# RP2350B.net
KiCad netlist of a schematic drawn in Altium Designer
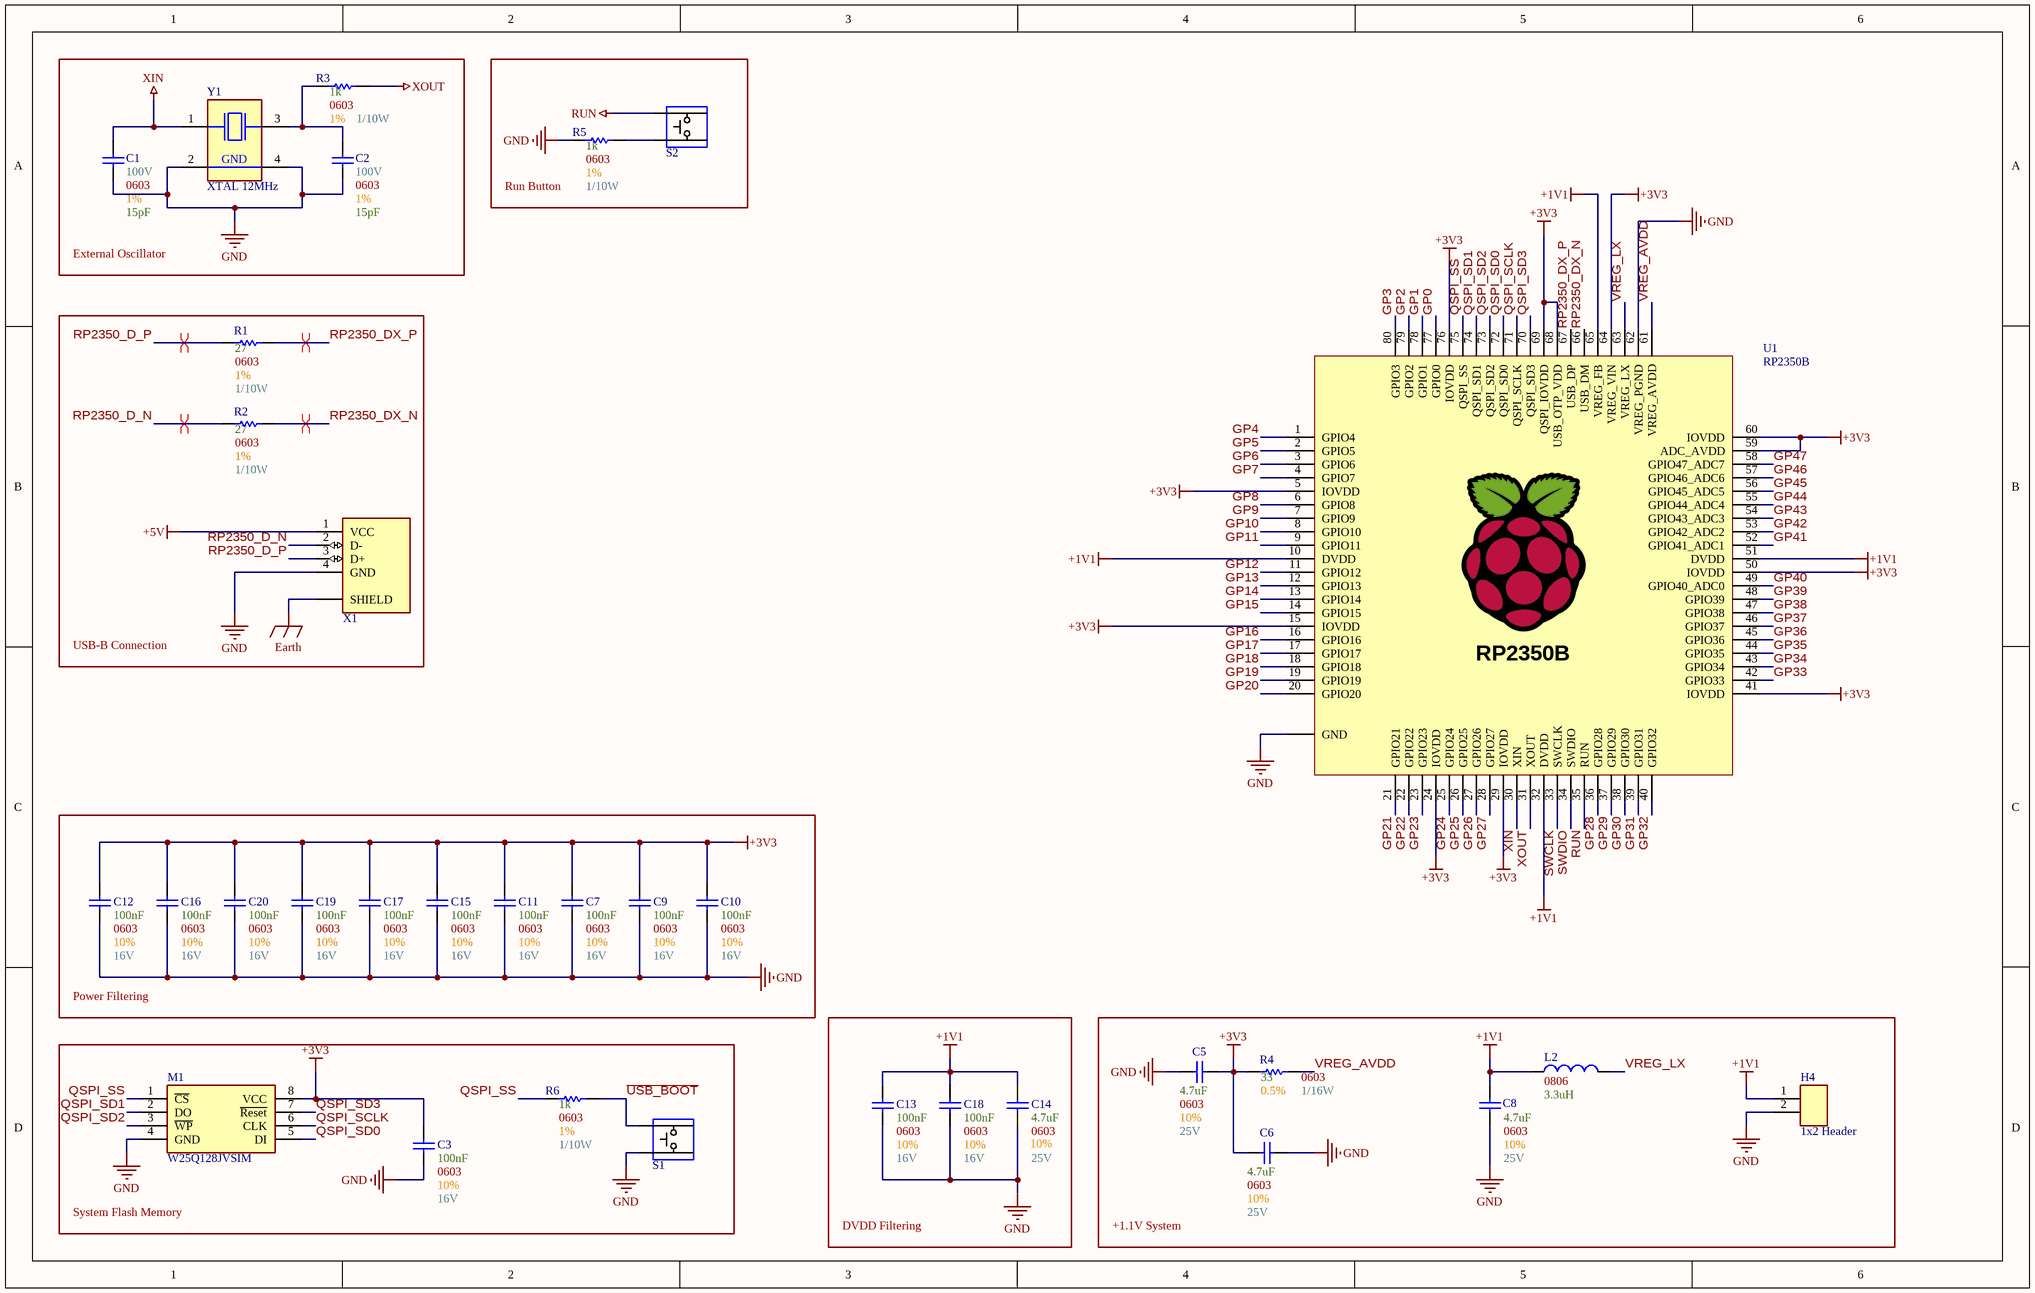
[diagram p0: RP2350B.SchDoc]

(export (version "E")
  (design (tool "Eeschema 10.0.6"))
  (components
    (comp (ref "C1")
      (value "[Cap] 0603 15pF 1% 100V")
      (footprint "[Cap] SMD 0603")
      (description "GCM1885C2A150FA16D")
      (fields
        (field (name "MAX VOLTAGE") "100V")
        (field (name "SIZE PACKAGE") "0603")
        (field (name "TOLERANCE") "1%")
        (field (name "CAPACITANCE") "15pF")
      )
      (libsource (lib "Capacitors") (part "[Cap] 0603 15pF 1% 100V"))
    )
    (comp (ref "C2")
      (value "[Cap] 0603 15pF 1% 100V")
      (footprint "[Cap] SMD 0603")
      (description "GCM1885C2A150FA16D")
      (fields
        (field (name "MAX VOLTAGE") "100V")
        (field (name "SIZE PACKAGE") "0603")
        (field (name "TOLERANCE") "1%")
        (field (name "CAPACITANCE") "15pF")
      )
      (libsource (lib "Capacitors") (part "[Cap] 0603 15pF 1% 100V"))
    )
    (comp (ref "C3")
      (value "[Cap] 0603 0.1uF 10% 16V")
      (footprint "[Cap] SMD 0603")
      (description "CC0603KRX7R7BB104")
      (fields
        (field (name "MAX VOLTAGE") "16V")
        (field (name "SIZE PACKAGE") "0603")
        (field (name "TOLERANCE") "10%")
        (field (name "CAPACITANCE") "100nF")
      )
      (libsource (lib "Capacitors") (part "[Cap] 0603 0.1uF 10% 16V"))
    )
    (comp (ref "C5")
      (value "[Cap] 0603 4.7uF 10% 25V")
      (footprint "[Cap] SMD 0603")
      (description "GRM188R61E475KE11D")
      (fields
        (field (name "MAX VOLTAGE") "25V")
        (field (name "SIZE PACKAGE") "0603")
        (field (name "TOLERANCE") "10%")
        (field (name "CAPACITANCE") "4.7uF")
      )
      (libsource (lib "Capacitors") (part "[Cap] 0603 4.7uF 10% 25V"))
    )
    (comp (ref "C6")
      (value "[Cap] 0603 4.7uF 10% 25V")
      (footprint "[Cap] SMD 0603")
      (description "GRM188R61E475KE11D")
      (fields
        (field (name "MAX VOLTAGE") "25V")
        (field (name "SIZE PACKAGE") "0603")
        (field (name "TOLERANCE") "10%")
        (field (name "CAPACITANCE") "4.7uF")
      )
      (libsource (lib "Capacitors") (part "[Cap] 0603 4.7uF 10% 25V"))
    )
    (comp (ref "C7")
      (value "[Cap] 0603 0.1uF 10% 16V")
      (footprint "[Cap] SMD 0603")
      (description "CC0603KRX7R7BB104")
      (fields
        (field (name "MAX VOLTAGE") "16V")
        (field (name "SIZE PACKAGE") "0603")
        (field (name "TOLERANCE") "10%")
        (field (name "CAPACITANCE") "100nF")
      )
      (libsource (lib "Capacitors") (part "[Cap] 0603 0.1uF 10% 16V"))
    )
    (comp (ref "C8")
      (value "[Cap] 0603 4.7uF 10% 25V")
      (footprint "[Cap] SMD 0603")
      (description "GRM188R61E475KE11D")
      (fields
        (field (name "MAX VOLTAGE") "25V")
        (field (name "SIZE PACKAGE") "0603")
        (field (name "TOLERANCE") "10%")
        (field (name "CAPACITANCE") "4.7uF")
      )
      (libsource (lib "Capacitors") (part "[Cap] 0603 4.7uF 10% 25V"))
    )
    (comp (ref "C9")
      (value "[Cap] 0603 0.1uF 10% 16V")
      (footprint "[Cap] SMD 0603")
      (description "CC0603KRX7R7BB104")
      (fields
        (field (name "MAX VOLTAGE") "16V")
        (field (name "SIZE PACKAGE") "0603")
        (field (name "TOLERANCE") "10%")
        (field (name "CAPACITANCE") "100nF")
      )
      (libsource (lib "Capacitors") (part "[Cap] 0603 0.1uF 10% 16V"))
    )
    (comp (ref "C10")
      (value "[Cap] 0603 0.1uF 10% 16V")
      (footprint "[Cap] SMD 0603")
      (description "CC0603KRX7R7BB104")
      (fields
        (field (name "MAX VOLTAGE") "16V")
        (field (name "SIZE PACKAGE") "0603")
        (field (name "TOLERANCE") "10%")
        (field (name "CAPACITANCE") "100nF")
      )
      (libsource (lib "Capacitors") (part "[Cap] 0603 0.1uF 10% 16V"))
    )
    (comp (ref "C11")
      (value "[Cap] 0603 0.1uF 10% 16V")
      (footprint "[Cap] SMD 0603")
      (description "CC0603KRX7R7BB104")
      (fields
        (field (name "MAX VOLTAGE") "16V")
        (field (name "SIZE PACKAGE") "0603")
        (field (name "TOLERANCE") "10%")
        (field (name "CAPACITANCE") "100nF")
      )
      (libsource (lib "Capacitors") (part "[Cap] 0603 0.1uF 10% 16V"))
    )
    (comp (ref "C12")
      (value "[Cap] 0603 0.1uF 10% 16V")
      (footprint "[Cap] SMD 0603")
      (description "CC0603KRX7R7BB104")
      (fields
        (field (name "MAX VOLTAGE") "16V")
        (field (name "SIZE PACKAGE") "0603")
        (field (name "TOLERANCE") "10%")
        (field (name "CAPACITANCE") "100nF")
      )
      (libsource (lib "Capacitors") (part "[Cap] 0603 0.1uF 10% 16V"))
    )
    (comp (ref "C13")
      (value "[Cap] 0603 0.1uF 10% 16V")
      (footprint "[Cap] SMD 0603")
      (description "CC0603KRX7R7BB104")
      (fields
        (field (name "MAX VOLTAGE") "16V")
        (field (name "SIZE PACKAGE") "0603")
        (field (name "TOLERANCE") "10%")
        (field (name "CAPACITANCE") "100nF")
      )
      (libsource (lib "Capacitors") (part "[Cap] 0603 0.1uF 10% 16V"))
    )
    (comp (ref "C14")
      (value "[Cap] 0603 4.7uF 10% 25V")
      (footprint "[Cap] SMD 0603")
      (description "GRM188R61E475KE11D")
      (fields
        (field (name "MAX VOLTAGE") "25V")
        (field (name "SIZE PACKAGE") "0603")
        (field (name "TOLERANCE") "10%")
        (field (name "CAPACITANCE") "4.7uF")
      )
      (libsource (lib "Capacitors") (part "[Cap] 0603 4.7uF 10% 25V"))
    )
    (comp (ref "C15")
      (value "[Cap] 0603 0.1uF 10% 16V")
      (footprint "[Cap] SMD 0603")
      (description "CC0603KRX7R7BB104")
      (fields
        (field (name "MAX VOLTAGE") "16V")
        (field (name "SIZE PACKAGE") "0603")
        (field (name "TOLERANCE") "10%")
        (field (name "CAPACITANCE") "100nF")
      )
      (libsource (lib "Capacitors") (part "[Cap] 0603 0.1uF 10% 16V"))
    )
    (comp (ref "C16")
      (value "[Cap] 0603 0.1uF 10% 16V")
      (footprint "[Cap] SMD 0603")
      (description "CC0603KRX7R7BB104")
      (fields
        (field (name "MAX VOLTAGE") "16V")
        (field (name "SIZE PACKAGE") "0603")
        (field (name "TOLERANCE") "10%")
        (field (name "CAPACITANCE") "100nF")
      )
      (libsource (lib "Capacitors") (part "[Cap] 0603 0.1uF 10% 16V"))
    )
    (comp (ref "C17")
      (value "[Cap] 0603 0.1uF 10% 16V")
      (footprint "[Cap] SMD 0603")
      (description "CC0603KRX7R7BB104")
      (fields
        (field (name "MAX VOLTAGE") "16V")
        (field (name "SIZE PACKAGE") "0603")
        (field (name "TOLERANCE") "10%")
        (field (name "CAPACITANCE") "100nF")
      )
      (libsource (lib "Capacitors") (part "[Cap] 0603 0.1uF 10% 16V"))
    )
    (comp (ref "C18")
      (value "[Cap] 0603 0.1uF 10% 16V")
      (footprint "[Cap] SMD 0603")
      (description "CC0603KRX7R7BB104")
      (fields
        (field (name "MAX VOLTAGE") "16V")
        (field (name "SIZE PACKAGE") "0603")
        (field (name "TOLERANCE") "10%")
        (field (name "CAPACITANCE") "100nF")
      )
      (libsource (lib "Capacitors") (part "[Cap] 0603 0.1uF 10% 16V"))
    )
    (comp (ref "C19")
      (value "[Cap] 0603 0.1uF 10% 16V")
      (footprint "[Cap] SMD 0603")
      (description "CC0603KRX7R7BB104")
      (fields
        (field (name "MAX VOLTAGE") "16V")
        (field (name "SIZE PACKAGE") "0603")
        (field (name "TOLERANCE") "10%")
        (field (name "CAPACITANCE") "100nF")
      )
      (libsource (lib "Capacitors") (part "[Cap] 0603 0.1uF 10% 16V"))
    )
    (comp (ref "C20")
      (value "[Cap] 0603 0.1uF 10% 16V")
      (footprint "[Cap] SMD 0603")
      (description "CC0603KRX7R7BB104")
      (fields
        (field (name "MAX VOLTAGE") "16V")
        (field (name "SIZE PACKAGE") "0603")
        (field (name "TOLERANCE") "10%")
        (field (name "CAPACITANCE") "100nF")
      )
      (libsource (lib "Capacitors") (part "[Cap] 0603 0.1uF 10% 16V"))
    )
    (comp (ref "H4")
      (value "1x2 Header")
      (footprint "[Header] 1x2 Male")
      (description "2.54mm pitch")
      (libsource (lib "Connectors") (part "[Header] 1x2 Male"))
    )
    (comp (ref "L2")
      (value "[3.3uH] SMD 0806 2.1A")
      (footprint "[Inductor] SMD 0806")
      (description "AOTA-B201610S3R3-101-T")
      (fields (field (name "PACKAGE") "0806") (field (name "INDUCTANCE") "3.3uH"))
      (libsource (lib "Inductors") (part "[3.3uH] SMD 0806 2.1A"))
    )
    (comp (ref "M1")
      (value "W25Q128JVSIM")
      (footprint "[Flash] 128MBit")
      (libsource (lib "Memory") (part "[Flash] 128MBit"))
    )
    (comp (ref "R1")
      (value "[27] SMD 0603 1% 1/10W")
      (footprint "[Res] SMD 0603")
      (description "MCT06030C2709FP500")
      (fields
        (field (name "WATTAGE") "1/10W")
        (field (name "TOLERANCE") "1%")
        (field (name "RESISTANCE") "27")
        (field (name "SIZE PACKAGE") "0603")
      )
      (libsource (lib "Resistors") (part "[27] SMD 0603 1% 1/10W"))
    )
    (comp (ref "R2")
      (value "[27] SMD 0603 1% 1/10W")
      (footprint "[Res] SMD 0603")
      (description "MCT06030C2709FP500")
      (fields
        (field (name "WATTAGE") "1/10W")
        (field (name "TOLERANCE") "1%")
        (field (name "RESISTANCE") "27")
        (field (name "SIZE PACKAGE") "0603")
      )
      (libsource (lib "Resistors") (part "[27] SMD 0603 1% 1/10W"))
    )
    (comp (ref "R3")
      (value "[1k] SMD 0603 1% 1/10W")
      (footprint "[Res] SMD 0603")
      (description "RMCF0603FT1K00")
      (fields
        (field (name "WATTAGE") "1/10W")
        (field (name "TOLERANCE") "1%")
        (field (name "RESISTANCE") "1k")
        (field (name "SIZE PACKAGE") "0603")
      )
      (libsource (lib "Resistors") (part "[1k] SMD 0603 1% 1/10W"))
    )
    (comp (ref "R4")
      (value "[33] SMD 0603 0.5% 1/16W")
      (footprint "[Res] SMD 0603")
      (description "RR0816Q-330-D")
      (fields
        (field (name "WATTAGE") "1/16W")
        (field (name "TOLERANCE") "0.5%")
        (field (name "RESISTANCE") "33")
        (field (name "SIZE PACKAGE") "0603")
      )
      (libsource (lib "Resistors") (part "[33] SMD 0603 0.5% 1/16W"))
    )
    (comp (ref "R5")
      (value "[1k] SMD 0603 1% 1/10W")
      (footprint "[Res] SMD 0603")
      (description "RMCF0603FT1K00")
      (fields
        (field (name "WATTAGE") "1/10W")
        (field (name "TOLERANCE") "1%")
        (field (name "RESISTANCE") "1k")
        (field (name "SIZE PACKAGE") "0603")
      )
      (libsource (lib "Resistors") (part "[1k] SMD 0603 1% 1/10W"))
    )
    (comp (ref "R6")
      (value "[1k] SMD 0603 1% 1/10W")
      (footprint "[Res] SMD 0603")
      (description "RMCF0603FT1K00")
      (fields
        (field (name "WATTAGE") "1/10W")
        (field (name "TOLERANCE") "1%")
        (field (name "RESISTANCE") "1k")
        (field (name "SIZE PACKAGE") "0603")
      )
      (libsource (lib "Resistors") (part "[1k] SMD 0603 1% 1/10W"))
    )
    (comp (ref "S1")
      (value "Standard pushbutton")
      (footprint "[SPST] Pushbutton")
      (libsource (lib "Switches") (part "[SPST] Pushbutton"))
    )
    (comp (ref "S2")
      (value "Standard pushbutton")
      (footprint "[SPST] Pushbutton")
      (libsource (lib "Switches") (part "[SPST] Pushbutton"))
    )
    (comp (ref "U1")
      (value "RP2350B")
      (footprint "[MCU] RP2350B")
      (description "QFN-80 Package")
      (libsource (lib "MCUs") (part "[MCU] RP2350B"))
    )
    (comp (ref "X1")
      (value "USB-B")
      (footprint "[USB] Type-B")
      (description "USB-B-S-F-B-TH")
      (libsource (lib "Connectors") (part "[USB] Type-B"))
    )
    (comp (ref "Y1")
      (value "XTAL 12MHz")
      (footprint "[Crystal] SMD 12MHz")
      (description "815-ABM8-272-T3")
      (libsource (lib "Crystals and Oscillators") (part "[Crystal] SMD 12MHz"))
    )
  )
  (nets
    (net (code "1") (name "+1V1") (class "Default")
      (node (ref "C13") (pin "2") (pinfunction "2_2") (pintype "passive"))
      (node (ref "C14") (pin "2") (pinfunction "2_2") (pintype "passive"))
      (node (ref "C18") (pin "2") (pinfunction "2_2") (pintype "passive"))
      (node (ref "C8") (pin "1") (pinfunction "1_1") (pintype "passive"))
      (node (ref "H4") (pin "1") (pintype "passive"))
      (node (ref "L2") (pin "1") (pinfunction "1_1") (pintype "passive"))
      (node (ref "U1") (pin "10") (pinfunction "DVDD_10") (pintype "passive"))
      (node (ref "U1") (pin "32") (pinfunction "DVDD_32") (pintype "passive"))
      (node (ref "U1") (pin "51") (pinfunction "DVDD_51") (pintype "passive"))
      (node (ref "U1") (pin "65") (pinfunction "VREG_FB_65") (pintype "passive"))
    )
    (net (code "2") (name "+3V3") (class "Default")
      (node (ref "C10") (pin "2") (pinfunction "2_2") (pintype "passive"))
      (node (ref "C11") (pin "2") (pinfunction "2_2") (pintype "passive"))
      (node (ref "C12") (pin "2") (pinfunction "2_2") (pintype "passive"))
      (node (ref "C15") (pin "2") (pinfunction "2_2") (pintype "passive"))
      (node (ref "C16") (pin "2") (pinfunction "2_2") (pintype "passive"))
      (node (ref "C17") (pin "2") (pinfunction "2_2") (pintype "passive"))
      (node (ref "C19") (pin "2") (pinfunction "2_2") (pintype "passive"))
      (node (ref "C20") (pin "2") (pinfunction "2_2") (pintype "passive"))
      (node (ref "C3") (pin "2") (pinfunction "2_2") (pintype "passive"))
      (node (ref "C5") (pin "1") (pinfunction "1_1") (pintype "passive"))
      (node (ref "C6") (pin "2") (pinfunction "2_2") (pintype "passive"))
      (node (ref "C7") (pin "2") (pinfunction "2_2") (pintype "passive"))
      (node (ref "C9") (pin "2") (pinfunction "2_2") (pintype "passive"))
      (node (ref "M1") (pin "8") (pinfunction "VCC_8") (pintype "passive"))
      (node (ref "R4") (pin "1") (pinfunction "1_1") (pintype "passive"))
      (node (ref "U1") (pin "15") (pinfunction "IOVDD_15") (pintype "passive"))
      (node (ref "U1") (pin "24") (pinfunction "IOVDD_24") (pintype "passive"))
      (node (ref "U1") (pin "29") (pinfunction "IOVDD_29") (pintype "passive"))
      (node (ref "U1") (pin "41") (pinfunction "IOVDD_41") (pintype "passive"))
      (node (ref "U1") (pin "5") (pinfunction "IOVDD_5") (pintype "passive"))
      (node (ref "U1") (pin "50") (pinfunction "IOVDD_50") (pintype "passive"))
      (node (ref "U1") (pin "59") (pinfunction "ADC_AVDD_59") (pintype "passive"))
      (node (ref "U1") (pin "60") (pinfunction "IOVDD_60") (pintype "passive"))
      (node (ref "U1") (pin "64") (pinfunction "VREG_VIN_64") (pintype "passive"))
      (node (ref "U1") (pin "68") (pinfunction "USB_OTP_VDD_68") (pintype "passive"))
      (node (ref "U1") (pin "69") (pinfunction "QSPI_IOVDD_69") (pintype "passive"))
      (node (ref "U1") (pin "76") (pinfunction "IOVDD_76") (pintype "passive"))
    )
    (net (code "3") (name "+5V") (class "Default")
      (node (ref "X1") (pin "1") (pinfunction "VCC_1") (pintype "power_in"))
    )
    (net (code "4") (name "/GP0") (class "Default")
      (node (ref "U1") (pin "77") (pinfunction "GPIO0_77") (pintype "passive"))
    )
    (net (code "5") (name "/GP1") (class "Default")
      (node (ref "U1") (pin "78") (pinfunction "GPIO1_78") (pintype "passive"))
    )
    (net (code "6") (name "/GP2") (class "Default")
      (node (ref "U1") (pin "79") (pinfunction "GPIO2_79") (pintype "passive"))
    )
    (net (code "7") (name "/GP3") (class "Default")
      (node (ref "U1") (pin "80") (pinfunction "GPIO3_80") (pintype "passive"))
    )
    (net (code "8") (name "/GP4") (class "Default")
      (node (ref "U1") (pin "1") (pinfunction "GPIO4_1") (pintype "passive"))
    )
    (net (code "9") (name "/GP5") (class "Default")
      (node (ref "U1") (pin "2") (pinfunction "GPIO5_2") (pintype "passive"))
    )
    (net (code "10") (name "/GP6") (class "Default")
      (node (ref "U1") (pin "3") (pinfunction "GPIO6_3") (pintype "passive"))
    )
    (net (code "11") (name "/GP7") (class "Default")
      (node (ref "U1") (pin "4") (pinfunction "GPIO7_4") (pintype "passive"))
    )
    (net (code "12") (name "/GP8") (class "Default")
      (node (ref "U1") (pin "6") (pinfunction "GPIO8_6") (pintype "passive"))
    )
    (net (code "13") (name "/GP9") (class "Default")
      (node (ref "U1") (pin "7") (pinfunction "GPIO9_7") (pintype "passive"))
    )
    (net (code "14") (name "/GP10") (class "Default")
      (node (ref "U1") (pin "8") (pinfunction "GPIO10_8") (pintype "passive"))
    )
    (net (code "15") (name "/GP11") (class "Default")
      (node (ref "U1") (pin "9") (pinfunction "GPIO11_9") (pintype "passive"))
    )
    (net (code "16") (name "/GP12") (class "Default")
      (node (ref "U1") (pin "11") (pinfunction "GPIO12_11") (pintype "passive"))
    )
    (net (code "17") (name "/GP13") (class "Default")
      (node (ref "U1") (pin "12") (pinfunction "GPIO13_12") (pintype "passive"))
    )
    (net (code "18") (name "/GP14") (class "Default")
      (node (ref "U1") (pin "13") (pinfunction "GPIO14_13") (pintype "passive"))
    )
    (net (code "19") (name "/GP15") (class "Default")
      (node (ref "U1") (pin "14") (pinfunction "GPIO15_14") (pintype "passive"))
    )
    (net (code "20") (name "/GP16") (class "Default")
      (node (ref "U1") (pin "16") (pinfunction "GPIO16_16") (pintype "passive"))
    )
    (net (code "21") (name "/GP17") (class "Default")
      (node (ref "U1") (pin "17") (pinfunction "GPIO17_17") (pintype "passive"))
    )
    (net (code "22") (name "/GP18") (class "Default")
      (node (ref "U1") (pin "18") (pinfunction "GPIO18_18") (pintype "passive"))
    )
    (net (code "23") (name "/GP19") (class "Default")
      (node (ref "U1") (pin "19") (pinfunction "GPIO19_19") (pintype "passive"))
    )
    (net (code "24") (name "/GP20") (class "Default")
      (node (ref "U1") (pin "20") (pinfunction "GPIO20_20") (pintype "passive"))
    )
    (net (code "25") (name "/GP21") (class "Default")
      (node (ref "U1") (pin "21") (pinfunction "GPIO21_21") (pintype "passive"))
    )
    (net (code "26") (name "/GP22") (class "Default")
      (node (ref "U1") (pin "22") (pinfunction "GPIO22_22") (pintype "passive"))
    )
    (net (code "27") (name "/GP23") (class "Default")
      (node (ref "U1") (pin "23") (pinfunction "GPIO23_23") (pintype "passive"))
    )
    (net (code "28") (name "/GP24") (class "Default")
      (node (ref "U1") (pin "25") (pinfunction "GPIO24_25") (pintype "passive"))
    )
    (net (code "29") (name "/GP25") (class "Default")
      (node (ref "U1") (pin "26") (pinfunction "GPIO25_26") (pintype "passive"))
    )
    (net (code "30") (name "/GP26") (class "Default")
      (node (ref "U1") (pin "27") (pinfunction "GPIO26_27") (pintype "passive"))
    )
    (net (code "31") (name "/GP27") (class "Default")
      (node (ref "U1") (pin "28") (pinfunction "GPIO27_28") (pintype "passive"))
    )
    (net (code "32") (name "/GP28") (class "Default")
      (node (ref "U1") (pin "36") (pinfunction "GPIO28_36") (pintype "passive"))
    )
    (net (code "33") (name "/GP29") (class "Default")
      (node (ref "U1") (pin "37") (pinfunction "GPIO29_37") (pintype "passive"))
    )
    (net (code "34") (name "/GP30") (class "Default")
      (node (ref "U1") (pin "38") (pinfunction "GPIO30_38") (pintype "passive"))
    )
    (net (code "35") (name "/GP31") (class "Default")
      (node (ref "U1") (pin "39") (pinfunction "GPIO31_39") (pintype "passive"))
    )
    (net (code "36") (name "/GP32") (class "Default")
      (node (ref "U1") (pin "40") (pinfunction "GPIO32_40") (pintype "passive"))
    )
    (net (code "37") (name "/GP33") (class "Default")
      (node (ref "U1") (pin "42") (pinfunction "GPIO33_42") (pintype "passive"))
    )
    (net (code "38") (name "/GP34") (class "Default")
      (node (ref "U1") (pin "43") (pinfunction "GPIO34_43") (pintype "passive"))
    )
    (net (code "39") (name "/GP35") (class "Default")
      (node (ref "U1") (pin "44") (pinfunction "GPIO35_44") (pintype "passive"))
    )
    (net (code "40") (name "/GP36") (class "Default")
      (node (ref "U1") (pin "45") (pinfunction "GPIO36_45") (pintype "passive"))
    )
    (net (code "41") (name "/GP37") (class "Default")
      (node (ref "U1") (pin "46") (pinfunction "GPIO37_46") (pintype "passive"))
    )
    (net (code "42") (name "/GP38") (class "Default")
      (node (ref "U1") (pin "47") (pinfunction "GPIO38_47") (pintype "passive"))
    )
    (net (code "43") (name "/GP39") (class "Default")
      (node (ref "U1") (pin "48") (pinfunction "GPIO39_48") (pintype "passive"))
    )
    (net (code "44") (name "/GP40") (class "Default")
      (node (ref "U1") (pin "49") (pinfunction "GPIO40_ADC0_49") (pintype "passive"))
    )
    (net (code "45") (name "/GP41") (class "Default")
      (node (ref "U1") (pin "52") (pinfunction "GPIO41_ADC1_52") (pintype "passive"))
    )
    (net (code "46") (name "/GP42") (class "Default")
      (node (ref "U1") (pin "53") (pinfunction "GPIO42_ADC2_53") (pintype "passive"))
    )
    (net (code "47") (name "/GP43") (class "Default")
      (node (ref "U1") (pin "54") (pinfunction "GPIO43_ADC3_54") (pintype "passive"))
    )
    (net (code "48") (name "/GP44") (class "Default")
      (node (ref "U1") (pin "55") (pinfunction "GPIO44_ADC4_55") (pintype "passive"))
    )
    (net (code "49") (name "/GP45") (class "Default")
      (node (ref "U1") (pin "56") (pinfunction "GPIO45_ADC5_56") (pintype "passive"))
    )
    (net (code "50") (name "/GP46") (class "Default")
      (node (ref "U1") (pin "57") (pinfunction "GPIO46_ADC6_57") (pintype "passive"))
    )
    (net (code "51") (name "/GP47") (class "Default")
      (node (ref "U1") (pin "58") (pinfunction "GPIO47_ADC7_58") (pintype "passive"))
    )
    (net (code "52") (name "/QSPI_SCLK") (class "Default")
      (node (ref "M1") (pin "6") (pinfunction "CLK_6") (pintype "passive"))
      (node (ref "U1") (pin "71") (pinfunction "QSPI_SCLK_71") (pintype "passive"))
    )
    (net (code "53") (name "/QSPI_SD0") (class "Default")
      (node (ref "M1") (pin "5") (pinfunction "DI_5") (pintype "passive"))
      (node (ref "U1") (pin "72") (pinfunction "QSPI_SD0_72") (pintype "passive"))
    )
    (net (code "54") (name "/QSPI_SD1") (class "Default")
      (node (ref "M1") (pin "2") (pinfunction "DO_2") (pintype "passive"))
      (node (ref "U1") (pin "74") (pinfunction "QSPI_SD1_74") (pintype "passive"))
    )
    (net (code "55") (name "/QSPI_SD2") (class "Default")
      (node (ref "M1") (pin "3") (pinfunction "~{WP}_3") (pintype "passive"))
      (node (ref "U1") (pin "73") (pinfunction "QSPI_SD2_73") (pintype "passive"))
    )
    (net (code "56") (name "/QSPI_SD3") (class "Default")
      (node (ref "M1") (pin "7") (pinfunction "~{Reset}_7") (pintype "passive"))
      (node (ref "U1") (pin "70") (pinfunction "QSPI_SD3_70") (pintype "passive"))
    )
    (net (code "57") (name "/QSPI_SS") (class "Default")
      (node (ref "M1") (pin "1") (pinfunction "~{CS}_1") (pintype "passive"))
      (node (ref "R6") (pin "1") (pinfunction "1_1") (pintype "passive"))
      (node (ref "U1") (pin "75") (pinfunction "QSPI_SS_75") (pintype "passive"))
    )
    (net (code "58") (name "/RP2350_DX_N") (class "Default")
      (node (ref "R2") (pin "2") (pinfunction "2_2") (pintype "passive"))
      (node (ref "U1") (pin "66") (pinfunction "USB_DM_66") (pintype "passive"))
    )
    (net (code "59") (name "/RP2350_DX_P") (class "Default")
      (node (ref "R1") (pin "2") (pinfunction "2_2") (pintype "passive"))
      (node (ref "U1") (pin "67") (pinfunction "USB_DP_67") (pintype "passive"))
    )
    (net (code "60") (name "/RP2350_D_N") (class "Default")
      (node (ref "R2") (pin "1") (pinfunction "1_1") (pintype "passive"))
      (node (ref "X1") (pin "2") (pinfunction "D-_2") (pintype "bidirectional"))
    )
    (net (code "61") (name "/RP2350_D_P") (class "Default")
      (node (ref "R1") (pin "1") (pinfunction "1_1") (pintype "passive"))
      (node (ref "X1") (pin "3") (pinfunction "D+_3") (pintype "bidirectional"))
    )
    (net (code "62") (name "/SWCLK") (class "Default")
      (node (ref "U1") (pin "33") (pinfunction "SWCLK_33") (pintype "passive"))
    )
    (net (code "63") (name "/SWDIO") (class "Default")
      (node (ref "U1") (pin "34") (pinfunction "SWDIO_34") (pintype "passive"))
    )
    (net (code "64") (name "/VREG_AVDD") (class "Default")
      (node (ref "R4") (pin "2") (pinfunction "2_2") (pintype "passive"))
      (node (ref "U1") (pin "61") (pinfunction "VREG_AVDD_61") (pintype "passive"))
    )
    (net (code "65") (name "/VREG_LX") (class "Default")
      (node (ref "L2") (pin "2") (pinfunction "2_2") (pintype "passive"))
      (node (ref "U1") (pin "63") (pinfunction "VREG_LX_63") (pintype "passive"))
    )
    (net (code "66") (name "/~{USB_BOOT}") (class "Default")
      (node (ref "R6") (pin "2") (pinfunction "2_2") (pintype "passive"))
      (node (ref "S1") (pin "1") (pintype "power_in"))
    )
    (net (code "67") (name "Earth") (class "Default")
      (node (ref "X1") (pin "MH") (pinfunction "SHIELD_MH") (pintype "passive"))
    )
    (net (code "68") (name "GND") (class "Default")
      (node (ref "C1") (pin "1") (pinfunction "1_1") (pintype "passive"))
      (node (ref "C10") (pin "1") (pinfunction "1_1") (pintype "passive"))
      (node (ref "C11") (pin "1") (pinfunction "1_1") (pintype "passive"))
      (node (ref "C12") (pin "1") (pinfunction "1_1") (pintype "passive"))
      (node (ref "C13") (pin "1") (pinfunction "1_1") (pintype "passive"))
      (node (ref "C14") (pin "1") (pinfunction "1_1") (pintype "passive"))
      (node (ref "C15") (pin "1") (pinfunction "1_1") (pintype "passive"))
      (node (ref "C16") (pin "1") (pinfunction "1_1") (pintype "passive"))
      (node (ref "C17") (pin "1") (pinfunction "1_1") (pintype "passive"))
      (node (ref "C18") (pin "1") (pinfunction "1_1") (pintype "passive"))
      (node (ref "C19") (pin "1") (pinfunction "1_1") (pintype "passive"))
      (node (ref "C2") (pin "1") (pinfunction "1_1") (pintype "passive"))
      (node (ref "C20") (pin "1") (pinfunction "1_1") (pintype "passive"))
      (node (ref "C3") (pin "1") (pinfunction "1_1") (pintype "passive"))
      (node (ref "C5") (pin "2") (pinfunction "2_2") (pintype "passive"))
      (node (ref "C6") (pin "1") (pinfunction "1_1") (pintype "passive"))
      (node (ref "C7") (pin "1") (pinfunction "1_1") (pintype "passive"))
      (node (ref "C8") (pin "2") (pinfunction "2_2") (pintype "passive"))
      (node (ref "C9") (pin "1") (pinfunction "1_1") (pintype "passive"))
      (node (ref "H4") (pin "2") (pintype "passive"))
      (node (ref "M1") (pin "4") (pinfunction "GND_4") (pintype "passive"))
      (node (ref "R5") (pin "1") (pinfunction "1_1") (pintype "passive"))
      (node (ref "S1") (pin "2") (pintype "power_in"))
      (node (ref "U1") (pin "62") (pinfunction "VREG_PGND_62") (pintype "passive"))
      (node (ref "U1") (pin "Pad") (pinfunction "GND_Pad") (pintype "passive"))
      (node (ref "X1") (pin "4") (pinfunction "GND_4") (pintype "power_in"))
      (node (ref "Y1") (pin "2") (pinfunction "GND_2") (pintype "power_in"))
      (node (ref "Y1") (pin "4") (pinfunction "GND_4") (pintype "power_in"))
    )
    (net (code "69") (name "Net-(R5-Pad2)") (class "Default")
      (node (ref "R5") (pin "2") (pinfunction "2_2") (pintype "passive"))
      (node (ref "S2") (pin "2") (pintype "power_in"))
    )
    (net (code "70") (name "Net-(Y1-XTAL2)") (class "Default")
      (node (ref "C2") (pin "2") (pinfunction "2_2") (pintype "passive"))
      (node (ref "R3") (pin "1") (pinfunction "1_1") (pintype "passive"))
      (node (ref "Y1") (pin "3") (pinfunction "XTAL2_3") (pintype "power_in"))
    )
    (net (code "71") (name "RUN") (class "Default")
      (node (ref "S2") (pin "1") (pintype "power_in"))
      (node (ref "U1") (pin "35") (pinfunction "RUN_35") (pintype "passive"))
    )
    (net (code "72") (name "XIN") (class "Default")
      (node (ref "C1") (pin "2") (pinfunction "2_2") (pintype "passive"))
      (node (ref "U1") (pin "30") (pinfunction "XIN_30") (pintype "passive"))
      (node (ref "Y1") (pin "1") (pinfunction "XTAL1_1") (pintype "power_in"))
    )
    (net (code "73") (name "XOUT") (class "Default")
      (node (ref "R3") (pin "2") (pinfunction "2_2") (pintype "passive"))
      (node (ref "U1") (pin "31") (pinfunction "XOUT_31") (pintype "passive"))
    )
  )
)
